# 620000200_-_GK_A_1_0.net
KiCad netlist of a schematic drawn in EAGLE
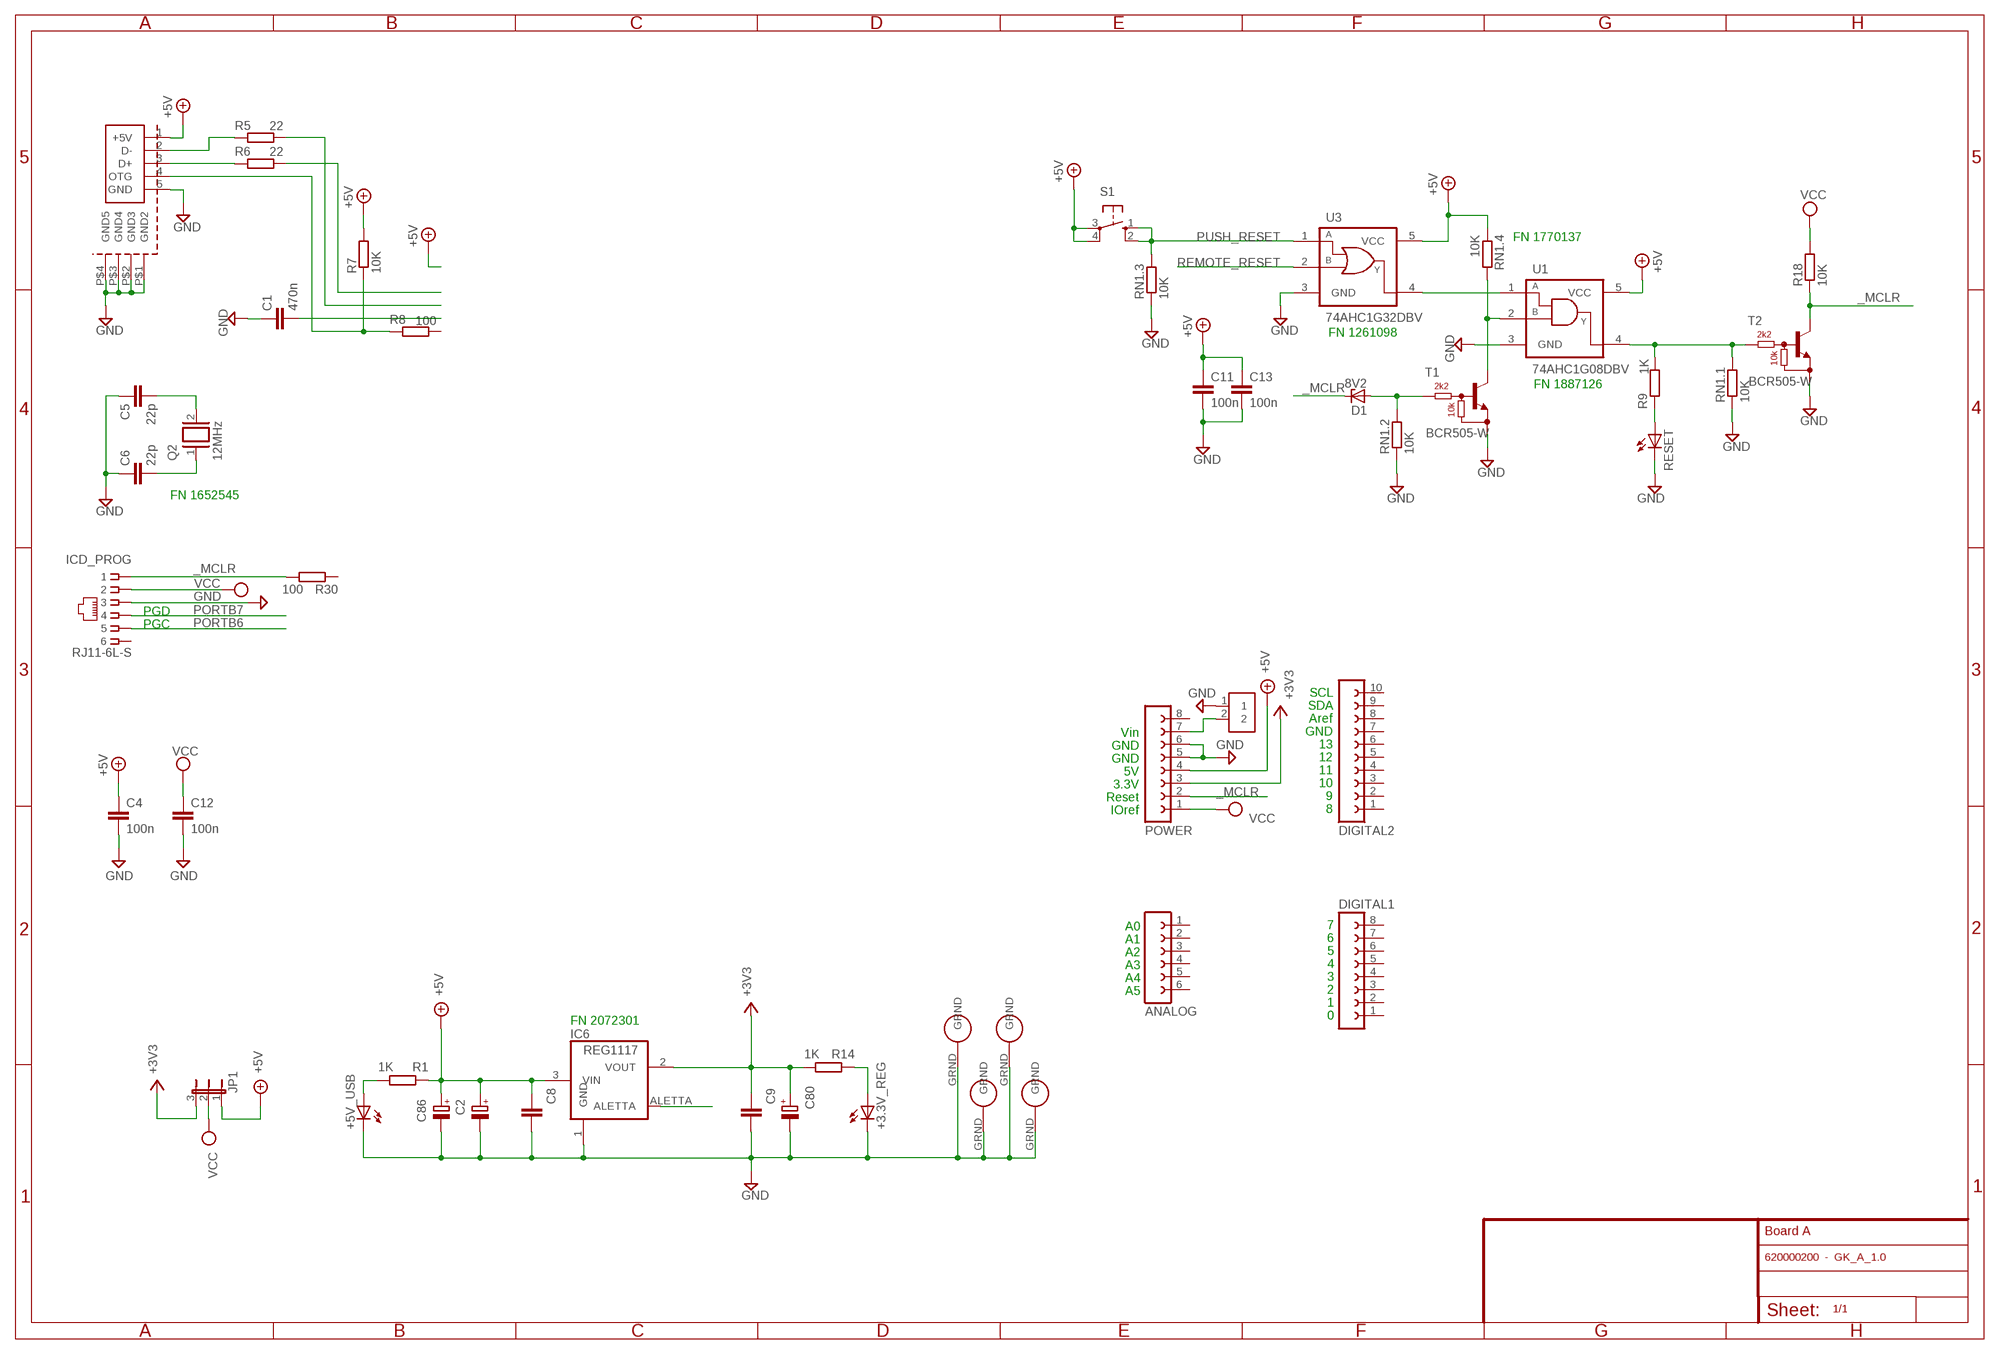
[diagram p0: schematic, sheet 1]

(export (version "E")
  (design (tool "Eeschema 10.0.6"))
  (components
    (comp (ref "+3.3V_REG")
      (value "LEDCHIPLED_0805")
      (footprint "eagle-import:CHIPLED_0805")
      (libsource (lib "eagle-import") (part "LEDCHIPLED_0805"))
    )
    (comp (ref "+5V_USB")
      (value "LEDCHIPLED_0805")
      (footprint "eagle-import:CHIPLED_0805")
      (libsource (lib "eagle-import") (part "LEDCHIPLED_0805"))
    )
    (comp (ref "ANALOG")
      (value "FE06-1")
      (footprint "eagle-import:FE06")
      (libsource (lib "eagle-import") (part "FE06-1"))
    )
    (comp (ref "C1")
      (value "470n")
      (footprint "eagle-import:C0805")
      (libsource (lib "eagle-import") (part "resistor_C-EUC0805"))
    )
    (comp (ref "C2")
      (value "47u")
      (footprint "eagle-import:153CLV-0605")
      (libsource (lib "eagle-import") (part "CPOL-EU153CLV-0605"))
    )
    (comp (ref "C4")
      (value "100n")
      (footprint "eagle-import:C0805")
      (libsource (lib "eagle-import") (part "resistor_C-EUC0805"))
    )
    (comp (ref "C5")
      (value "22p")
      (footprint "eagle-import:C0805")
      (libsource (lib "eagle-import") (part "C-EUC0805"))
    )
    (comp (ref "C6")
      (value "22p")
      (footprint "eagle-import:C0805")
      (libsource (lib "eagle-import") (part "C-EUC0805"))
    )
    (comp (ref "C8")
      (value "100n")
      (footprint "eagle-import:C0805K")
      (libsource (lib "eagle-import") (part "C-EUC0805K"))
    )
    (comp (ref "C9")
      (value "100n")
      (footprint "eagle-import:C0805K")
      (libsource (lib "eagle-import") (part "C-EUC0805K"))
    )
    (comp (ref "C11")
      (value "100n")
      (footprint "eagle-import:C0805")
      (libsource (lib "eagle-import") (part "resistor_C-EUC0805"))
    )
    (comp (ref "C12")
      (value "100n")
      (footprint "eagle-import:C0805")
      (libsource (lib "eagle-import") (part "resistor_C-EUC0805"))
    )
    (comp (ref "C13")
      (value "100n")
      (footprint "eagle-import:C0805")
      (libsource (lib "eagle-import") (part "resistor_C-EUC0805"))
    )
    (comp (ref "C80")
      (value "47u")
      (footprint "eagle-import:153CLV-0605")
      (libsource (lib "eagle-import") (part "CPOL-EU153CLV-0605"))
    )
    (comp (ref "C86")
      (value "47u")
      (footprint "eagle-import:153CLV-0605")
      (libsource (lib "eagle-import") (part "CPOL-EU153CLV-0605"))
    )
    (comp (ref "D1")
      (value "8V2")
      (footprint "eagle-import:SOT23")
      (libsource (lib "eagle-import") (part "ZENER-DIODESOT23"))
    )
    (comp (ref "DIGITAL1")
      (value "FE08-1")
      (footprint "eagle-import:FE08")
      (libsource (lib "eagle-import") (part "FE08-1"))
    )
    (comp (ref "DIGITAL2")
      (value "FE10-1")
      (footprint "eagle-import:FE10")
      (libsource (lib "eagle-import") (part "FE10-1"))
    )
    (comp (ref "IC6")
      (value "REG1117")
      (footprint "eagle-import:REG1117")
      (libsource (lib "eagle-import") (part "REG1117"))
    )
    (comp (ref "ICD_PROG")
      (value "RJ11-6L-S")
      (footprint "eagle-import:RJ11-NO_SHIELD")
      (fields (field (name "MF") "TYCO ELECTRONICS"))
      (libsource (lib "eagle-import") (part "RJ11-6L-S"))
    )
    (comp (ref "JP1")
      (value "JP2E")
      (footprint "eagle-import:JP2")
      (libsource (lib "eagle-import") (part "JP2E"))
    )
    (comp (ref "POWER")
      (value "FE08-1")
      (footprint "eagle-import:FE08")
      (libsource (lib "eagle-import") (part "FE08-1"))
    )
    (comp (ref "Q2")
      (value "12MHz")
      (footprint "eagle-import:QS")
      (libsource (lib "eagle-import") (part "XTAL/S"))
    )
    (comp (ref "R1")
      (value "1K")
      (footprint "eagle-import:R0805W")
      (libsource (lib "eagle-import") (part "R-EU_R0805W"))
    )
    (comp (ref "R5")
      (value "22")
      (footprint "eagle-import:R0805W")
      (libsource (lib "eagle-import") (part "R-EU_R0805W"))
    )
    (comp (ref "R6")
      (value "22")
      (footprint "eagle-import:R0805W")
      (libsource (lib "eagle-import") (part "R-EU_R0805W"))
    )
    (comp (ref "R7")
      (value "10K")
      (footprint "eagle-import:R0805")
      (libsource (lib "eagle-import") (part "R-EU_R0805"))
    )
    (comp (ref "R8")
      (value "100")
      (footprint "eagle-import:R0805")
      (libsource (lib "eagle-import") (part "R-EU_R0805"))
    )
    (comp (ref "R9")
      (value "1K")
      (footprint "eagle-import:R0805")
      (libsource (lib "eagle-import") (part "R-EU_R0805"))
    )
    (comp (ref "R14")
      (value "1K")
      (footprint "eagle-import:R0805W")
      (libsource (lib "eagle-import") (part "R-EU_R0805W"))
    )
    (comp (ref "R18")
      (value "10K")
      (footprint "eagle-import:R0805")
      (libsource (lib "eagle-import") (part "R-EU_R0805"))
    )
    (comp (ref "R30")
      (value "100")
      (footprint "eagle-import:R0805W")
      (libsource (lib "eagle-import") (part "R-EU_R0805W"))
    )
    (comp (ref "RESET")
      (value "LEDCHIPLED_0805")
      (footprint "eagle-import:CHIPLED_0805")
      (libsource (lib "eagle-import") (part "LEDCHIPLED_0805"))
    )
    (comp (ref "RN1")
      (value "10K")
      (footprint "eagle-import:CTS-744_083")
      (libsource (lib "eagle-import") (part "RN_EU-4"))
    )
    (comp (ref "S1")
      (value "10-XX")
      (footprint "eagle-import:B3F-10XX")
      (libsource (lib "eagle-import") (part "10-XX"))
    )
    (comp (ref "T1")
      (value "BCR505-W")
      (footprint "eagle-import:SOT23-W_INFINEON")
      (libsource (lib "eagle-import") (part "BCR505-W"))
    )
    (comp (ref "T2")
      (value "BCR505-W")
      (footprint "eagle-import:SOT23-W_INFINEON")
      (libsource (lib "eagle-import") (part "BCR505-W"))
    )
    (comp (ref "U$1")
      (value "GKHOLE")
      (footprint "eagle-import:GKHOLE")
      (libsource (lib "eagle-import") (part "GKHOLE"))
    )
    (comp (ref "U$2")
      (value "GKHOLE")
      (footprint "eagle-import:GKHOLE")
      (libsource (lib "eagle-import") (part "GKHOLE"))
    )
    (comp (ref "U$3")
      (value "GKHOLE")
      (footprint "eagle-import:GKHOLE")
      (libsource (lib "eagle-import") (part "GKHOLE"))
    )
    (comp (ref "U$4")
      (value "GKHOLE")
      (footprint "eagle-import:GKHOLE")
      (libsource (lib "eagle-import") (part "GKHOLE"))
    )
    (comp (ref "U$7")
      (value "USB_SMD")
      (footprint "eagle-import:USB_MINI_SMD")
      (libsource (lib "eagle-import") (part "USB_SMD"))
    )
    (comp (ref "U$8")
      (value "GKHEAD2")
      (footprint "eagle-import:HEAD2")
      (libsource (lib "eagle-import") (part "GKHEAD2"))
    )
    (comp (ref "U1")
      (value "74AHC1G08DBV")
      (footprint "eagle-import:SOT23-5")
      (libsource (lib "eagle-import") (part "74AHC1G08DBV"))
    )
    (comp (ref "U3")
      (value "74AHC1G32DBV")
      (footprint "eagle-import:SOT23-5")
      (libsource (lib "eagle-import") (part "74AHC1G32DBV"))
    )
  )
  (nets
    (net (code "1") (name "+3V3") (class "Default")
      (node (ref "C80") (pin "+") (pinfunction "+_+") (pintype "passive"))
      (node (ref "C9") (pin "2") (pinfunction "2_2") (pintype "passive"))
      (node (ref "IC6") (pin "2") (pinfunction "VOUT_2") (pintype "output"))
      (node (ref "JP1") (pin "3") (pinfunction "3_3") (pintype "passive"))
      (node (ref "POWER") (pin "3") (pinfunction "3_3") (pintype "passive"))
      (node (ref "R14") (pin "1") (pinfunction "1_1") (pintype "passive"))
    )
    (net (code "2") (name "+5V") (class "Default")
      (node (ref "C11") (pin "1") (pinfunction "1_1") (pintype "passive"))
      (node (ref "C13") (pin "1") (pinfunction "1_1") (pintype "passive"))
      (node (ref "C2") (pin "+") (pinfunction "+_+") (pintype "passive"))
      (node (ref "C4") (pin "1") (pinfunction "1_1") (pintype "passive"))
      (node (ref "C8") (pin "2") (pinfunction "2_2") (pintype "passive"))
      (node (ref "C86") (pin "+") (pinfunction "+_+") (pintype "passive"))
      (node (ref "IC6") (pin "3") (pinfunction "VIN_3") (pintype "input"))
      (node (ref "JP1") (pin "1") (pinfunction "1_1") (pintype "passive"))
      (node (ref "POWER") (pin "4") (pinfunction "4_4") (pintype "passive"))
      (node (ref "R1") (pin "2") (pinfunction "2_2") (pintype "passive"))
      (node (ref "R7") (pin "2") (pinfunction "2_2") (pintype "passive"))
      (node (ref "RN1") (pin "4") (pinfunction "1_4") (pintype "passive"))
      (node (ref "S1") (pin "3") (pinfunction "P_3") (pintype "passive"))
      (node (ref "S1") (pin "4") (pinfunction "P1_4") (pintype "passive"))
      (node (ref "U$7") (pin "1") (pinfunction "+5V_1") (pintype "bidirectional"))
      (node (ref "U1") (pin "5") (pinfunction "VCC_5") (pintype "power_in"))
      (node (ref "U3") (pin "5") (pinfunction "VCC_5") (pintype "power_in"))
    )
    (net (code "3") (name "/PORTB6") (class "Default")
      (node (ref "ICD_PROG") (pin "5") (pinfunction "5_5") (pintype "passive"))
    )
    (net (code "4") (name "/PORTB7") (class "Default")
      (node (ref "ICD_PROG") (pin "4") (pinfunction "4_4") (pintype "passive"))
    )
    (net (code "5") (name "/PUSH_RESET") (class "Default")
      (node (ref "RN1") (pin "6") (pinfunction "2_6") (pintype "passive"))
      (node (ref "S1") (pin "1") (pinfunction "S_1") (pintype "passive"))
      (node (ref "S1") (pin "2") (pinfunction "S1_2") (pintype "passive"))
      (node (ref "U3") (pin "1") (pinfunction "A_1") (pintype "input"))
    )
    (net (code "6") (name "/REMOTE_RESET") (class "Default")
      (node (ref "U3") (pin "2") (pinfunction "B_2") (pintype "input"))
    )
    (net (code "7") (name "/_MCLR") (class "Default")
      (node (ref "D1") (pin "3") (pinfunction "C_3") (pintype "passive"))
      (node (ref "ICD_PROG") (pin "1") (pinfunction "1_1") (pintype "passive"))
      (node (ref "POWER") (pin "2") (pinfunction "2_2") (pintype "passive"))
      (node (ref "R18") (pin "1") (pinfunction "1_1") (pintype "passive"))
      (node (ref "R30") (pin "1") (pinfunction "1_1") (pintype "passive"))
      (node (ref "T2") (pin "3") (pinfunction "C_3") (pintype "passive"))
    )
    (net (code "8") (name "GND") (class "Default")
      (node (ref "+3.3V_REG") (pin "C") (pinfunction "C_C") (pintype "passive"))
      (node (ref "+5V_USB") (pin "C") (pinfunction "C_C") (pintype "passive"))
      (node (ref "C1") (pin "1") (pinfunction "1_1") (pintype "passive"))
      (node (ref "C11") (pin "2") (pinfunction "2_2") (pintype "passive"))
      (node (ref "C12") (pin "2") (pinfunction "2_2") (pintype "passive"))
      (node (ref "C13") (pin "2") (pinfunction "2_2") (pintype "passive"))
      (node (ref "C2") (pin "-") (pinfunction "-_-") (pintype "passive"))
      (node (ref "C4") (pin "2") (pinfunction "2_2") (pintype "passive"))
      (node (ref "C5") (pin "1") (pinfunction "1_1") (pintype "passive"))
      (node (ref "C6") (pin "1") (pinfunction "1_1") (pintype "passive"))
      (node (ref "C8") (pin "1") (pinfunction "1_1") (pintype "passive"))
      (node (ref "C80") (pin "-") (pinfunction "-_-") (pintype "passive"))
      (node (ref "C86") (pin "-") (pinfunction "-_-") (pintype "passive"))
      (node (ref "C9") (pin "1") (pinfunction "1_1") (pintype "passive"))
      (node (ref "IC6") (pin "1") (pinfunction "GND_1") (pintype "power_in"))
      (node (ref "ICD_PROG") (pin "3") (pinfunction "3_3") (pintype "passive"))
      (node (ref "POWER") (pin "5") (pinfunction "5_5") (pintype "passive"))
      (node (ref "POWER") (pin "6") (pinfunction "6_6") (pintype "passive"))
      (node (ref "RESET") (pin "C") (pinfunction "C_C") (pintype "passive"))
      (node (ref "RN1") (pin "1") (pinfunction "1_1") (pintype "passive"))
      (node (ref "RN1") (pin "2") (pinfunction "1_2") (pintype "passive"))
      (node (ref "RN1") (pin "3") (pinfunction "1_3") (pintype "passive"))
      (node (ref "T1") (pin "2") (pinfunction "E_2") (pintype "passive"))
      (node (ref "T2") (pin "2") (pinfunction "E_2") (pintype "passive"))
      (node (ref "U$1") (pin "GRND") (pinfunction "GRND_GRND") (pintype "power_in"))
      (node (ref "U$2") (pin "GRND") (pinfunction "GRND_GRND") (pintype "power_in"))
      (node (ref "U$3") (pin "GRND") (pinfunction "GRND_GRND") (pintype "power_in"))
      (node (ref "U$4") (pin "GRND") (pinfunction "GRND_GRND") (pintype "power_in"))
      (node (ref "U$7") (pin "5") (pinfunction "GND_5") (pintype "bidirectional"))
      (node (ref "U$7") (pin "P$1") (pinfunction "GND2_P$1") (pintype "bidirectional"))
      (node (ref "U$7") (pin "P$2") (pinfunction "GND3_P$2") (pintype "bidirectional"))
      (node (ref "U$7") (pin "P$3") (pinfunction "GND4_P$3") (pintype "bidirectional"))
      (node (ref "U$7") (pin "P$4") (pinfunction "GND5_P$4") (pintype "bidirectional"))
      (node (ref "U$8") (pin "1") (pinfunction "1_1") (pintype "bidirectional"))
      (node (ref "U1") (pin "3") (pinfunction "GND_3") (pintype "power_in"))
      (node (ref "U3") (pin "3") (pinfunction "GND_3") (pintype "power_in"))
    )
    (net (code "9") (name "Net-(+3.3V_REG-PadA)") (class "Default")
      (node (ref "+3.3V_REG") (pin "A") (pinfunction "A_A") (pintype "passive"))
      (node (ref "R14") (pin "2") (pinfunction "2_2") (pintype "passive"))
    )
    (net (code "10") (name "Net-(+5V_USB-PadA)") (class "Default")
      (node (ref "+5V_USB") (pin "A") (pinfunction "A_A") (pintype "passive"))
      (node (ref "R1") (pin "1") (pinfunction "1_1") (pintype "passive"))
    )
    (net (code "11") (name "Net-(C5-Pad2)") (class "Default")
      (node (ref "C5") (pin "2") (pinfunction "2_2") (pintype "passive"))
      (node (ref "Q2") (pin "2") (pinfunction "2_2") (pintype "passive"))
    )
    (net (code "12") (name "Net-(C6-Pad2)") (class "Default")
      (node (ref "C6") (pin "2") (pinfunction "2_2") (pintype "passive"))
      (node (ref "Q2") (pin "1") (pinfunction "1_1") (pintype "passive"))
    )
    (net (code "13") (name "Net-(D1-A)") (class "Default")
      (node (ref "D1") (pin "1") (pinfunction "A_1") (pintype "passive"))
      (node (ref "RN1") (pin "7") (pinfunction "2_7") (pintype "passive"))
      (node (ref "T1") (pin "1") (pinfunction "B_1") (pintype "passive"))
    )
    (net (code "14") (name "Net-(POWER-Pad7)") (class "Default")
      (node (ref "POWER") (pin "7") (pinfunction "7_7") (pintype "passive"))
      (node (ref "U$8") (pin "2") (pinfunction "2_2") (pintype "bidirectional"))
    )
    (net (code "15") (name "Net-(R9-Pad2)") (class "Default")
      (node (ref "R9") (pin "2") (pinfunction "2_2") (pintype "passive"))
      (node (ref "RESET") (pin "A") (pinfunction "A_A") (pintype "passive"))
    )
    (net (code "16") (name "Net-(RN1A-2)") (class "Default")
      (node (ref "R9") (pin "1") (pinfunction "1_1") (pintype "passive"))
      (node (ref "RN1") (pin "8") (pinfunction "2_8") (pintype "passive"))
      (node (ref "T2") (pin "1") (pinfunction "B_1") (pintype "passive"))
      (node (ref "U1") (pin "4") (pinfunction "Y_4") (pintype "output"))
    )
    (net (code "17") (name "Net-(RN1D-2)") (class "Default")
      (node (ref "RN1") (pin "5") (pinfunction "2_5") (pintype "passive"))
      (node (ref "T1") (pin "3") (pinfunction "C_3") (pintype "passive"))
      (node (ref "U1") (pin "2") (pinfunction "B_2") (pintype "input"))
    )
    (net (code "18") (name "Net-(U$7-D+)") (class "Default")
      (node (ref "R6") (pin "2") (pinfunction "2_2") (pintype "passive"))
      (node (ref "U$7") (pin "3") (pinfunction "D+_3") (pintype "bidirectional"))
    )
    (net (code "19") (name "Net-(U$7-D-)") (class "Default")
      (node (ref "R5") (pin "2") (pinfunction "2_2") (pintype "passive"))
      (node (ref "U$7") (pin "2") (pinfunction "D-_2") (pintype "bidirectional"))
    )
    (net (code "20") (name "Net-(U$7-OTG)") (class "Default")
      (node (ref "R7") (pin "1") (pinfunction "1_1") (pintype "passive"))
      (node (ref "R8") (pin "1") (pinfunction "1_1") (pintype "passive"))
      (node (ref "U$7") (pin "4") (pinfunction "OTG_4") (pintype "bidirectional"))
    )
    (net (code "21") (name "Net-(U1-A)") (class "Default")
      (node (ref "U1") (pin "1") (pinfunction "A_1") (pintype "input"))
      (node (ref "U3") (pin "4") (pinfunction "Y_4") (pintype "output"))
    )
    (net (code "22") (name "VCC") (class "Default")
      (node (ref "C12") (pin "1") (pinfunction "1_1") (pintype "passive"))
      (node (ref "ICD_PROG") (pin "2") (pinfunction "2_2") (pintype "passive"))
      (node (ref "JP1") (pin "2") (pinfunction "2_2") (pintype "passive"))
      (node (ref "POWER") (pin "1") (pinfunction "1_1") (pintype "passive"))
      (node (ref "R18") (pin "2") (pinfunction "2_2") (pintype "passive"))
    )
    (net (code "23") (name "unconnected-(ANALOG-Pad1)") (class "Default")
      (node (ref "ANALOG") (pin "1") (pinfunction "1_1") (pintype "passive"))
    )
    (net (code "24") (name "unconnected-(ANALOG-Pad2)") (class "Default")
      (node (ref "ANALOG") (pin "2") (pinfunction "2_2") (pintype "passive"))
    )
    (net (code "25") (name "unconnected-(ANALOG-Pad3)") (class "Default")
      (node (ref "ANALOG") (pin "3") (pinfunction "3_3") (pintype "passive"))
    )
    (net (code "26") (name "unconnected-(ANALOG-Pad4)") (class "Default")
      (node (ref "ANALOG") (pin "4") (pinfunction "4_4") (pintype "passive"))
    )
    (net (code "27") (name "unconnected-(ANALOG-Pad5)") (class "Default")
      (node (ref "ANALOG") (pin "5") (pinfunction "5_5") (pintype "passive"))
    )
    (net (code "28") (name "unconnected-(ANALOG-Pad6)") (class "Default")
      (node (ref "ANALOG") (pin "6") (pinfunction "6_6") (pintype "passive"))
    )
    (net (code "29") (name "unconnected-(C1-Pad2)") (class "Default")
      (node (ref "C1") (pin "2") (pinfunction "2_2") (pintype "passive"))
    )
    (net (code "30") (name "unconnected-(DIGITAL1-Pad1)") (class "Default")
      (node (ref "DIGITAL1") (pin "1") (pinfunction "1_1") (pintype "passive"))
    )
    (net (code "31") (name "unconnected-(DIGITAL1-Pad2)") (class "Default")
      (node (ref "DIGITAL1") (pin "2") (pinfunction "2_2") (pintype "passive"))
    )
    (net (code "32") (name "unconnected-(DIGITAL1-Pad3)") (class "Default")
      (node (ref "DIGITAL1") (pin "3") (pinfunction "3_3") (pintype "passive"))
    )
    (net (code "33") (name "unconnected-(DIGITAL1-Pad4)") (class "Default")
      (node (ref "DIGITAL1") (pin "4") (pinfunction "4_4") (pintype "passive"))
    )
    (net (code "34") (name "unconnected-(DIGITAL1-Pad5)") (class "Default")
      (node (ref "DIGITAL1") (pin "5") (pinfunction "5_5") (pintype "passive"))
    )
    (net (code "35") (name "unconnected-(DIGITAL1-Pad6)") (class "Default")
      (node (ref "DIGITAL1") (pin "6") (pinfunction "6_6") (pintype "passive"))
    )
    (net (code "36") (name "unconnected-(DIGITAL1-Pad7)") (class "Default")
      (node (ref "DIGITAL1") (pin "7") (pinfunction "7_7") (pintype "passive"))
    )
    (net (code "37") (name "unconnected-(DIGITAL1-Pad8)") (class "Default")
      (node (ref "DIGITAL1") (pin "8") (pinfunction "8_8") (pintype "passive"))
    )
    (net (code "38") (name "unconnected-(DIGITAL2-Pad1)") (class "Default")
      (node (ref "DIGITAL2") (pin "1") (pinfunction "1_1") (pintype "passive"))
    )
    (net (code "39") (name "unconnected-(DIGITAL2-Pad2)") (class "Default")
      (node (ref "DIGITAL2") (pin "2") (pinfunction "2_2") (pintype "passive"))
    )
    (net (code "40") (name "unconnected-(DIGITAL2-Pad3)") (class "Default")
      (node (ref "DIGITAL2") (pin "3") (pinfunction "3_3") (pintype "passive"))
    )
    (net (code "41") (name "unconnected-(DIGITAL2-Pad4)") (class "Default")
      (node (ref "DIGITAL2") (pin "4") (pinfunction "4_4") (pintype "passive"))
    )
    (net (code "42") (name "unconnected-(DIGITAL2-Pad5)") (class "Default")
      (node (ref "DIGITAL2") (pin "5") (pinfunction "5_5") (pintype "passive"))
    )
    (net (code "43") (name "unconnected-(DIGITAL2-Pad6)") (class "Default")
      (node (ref "DIGITAL2") (pin "6") (pinfunction "6_6") (pintype "passive"))
    )
    (net (code "44") (name "unconnected-(DIGITAL2-Pad7)") (class "Default")
      (node (ref "DIGITAL2") (pin "7") (pinfunction "7_7") (pintype "passive"))
    )
    (net (code "45") (name "unconnected-(DIGITAL2-Pad8)") (class "Default")
      (node (ref "DIGITAL2") (pin "8") (pinfunction "8_8") (pintype "passive"))
    )
    (net (code "46") (name "unconnected-(DIGITAL2-Pad9)") (class "Default")
      (node (ref "DIGITAL2") (pin "9") (pinfunction "9_9") (pintype "passive"))
    )
    (net (code "47") (name "unconnected-(DIGITAL2-Pad10)") (class "Default")
      (node (ref "DIGITAL2") (pin "10") (pinfunction "10_10") (pintype "passive"))
    )
    (net (code "48") (name "unconnected-(IC6-PadALETTA)") (class "Default")
      (node (ref "IC6") (pin "ALETTA") (pinfunction "ALETTA_ALETTA") (pintype "bidirectional"))
    )
    (net (code "49") (name "unconnected-(ICD_PROG-Pad6)") (class "Default")
      (node (ref "ICD_PROG") (pin "6") (pinfunction "6_6") (pintype "passive"))
    )
    (net (code "50") (name "unconnected-(POWER-Pad8)") (class "Default")
      (node (ref "POWER") (pin "8") (pinfunction "8_8") (pintype "passive"))
    )
    (net (code "51") (name "unconnected-(R5-Pad1)") (class "Default")
      (node (ref "R5") (pin "1") (pinfunction "1_1") (pintype "passive"))
    )
    (net (code "52") (name "unconnected-(R6-Pad1)") (class "Default")
      (node (ref "R6") (pin "1") (pinfunction "1_1") (pintype "passive"))
    )
    (net (code "53") (name "unconnected-(R8-Pad2)") (class "Default")
      (node (ref "R8") (pin "2") (pinfunction "2_2") (pintype "passive"))
    )
    (net (code "54") (name "unconnected-(R30-Pad2)") (class "Default")
      (node (ref "R30") (pin "2") (pinfunction "2_2") (pintype "passive"))
    )
  )
)
